# umodular_ctrl16.net
KiCad netlist of a schematic drawn in EAGLE
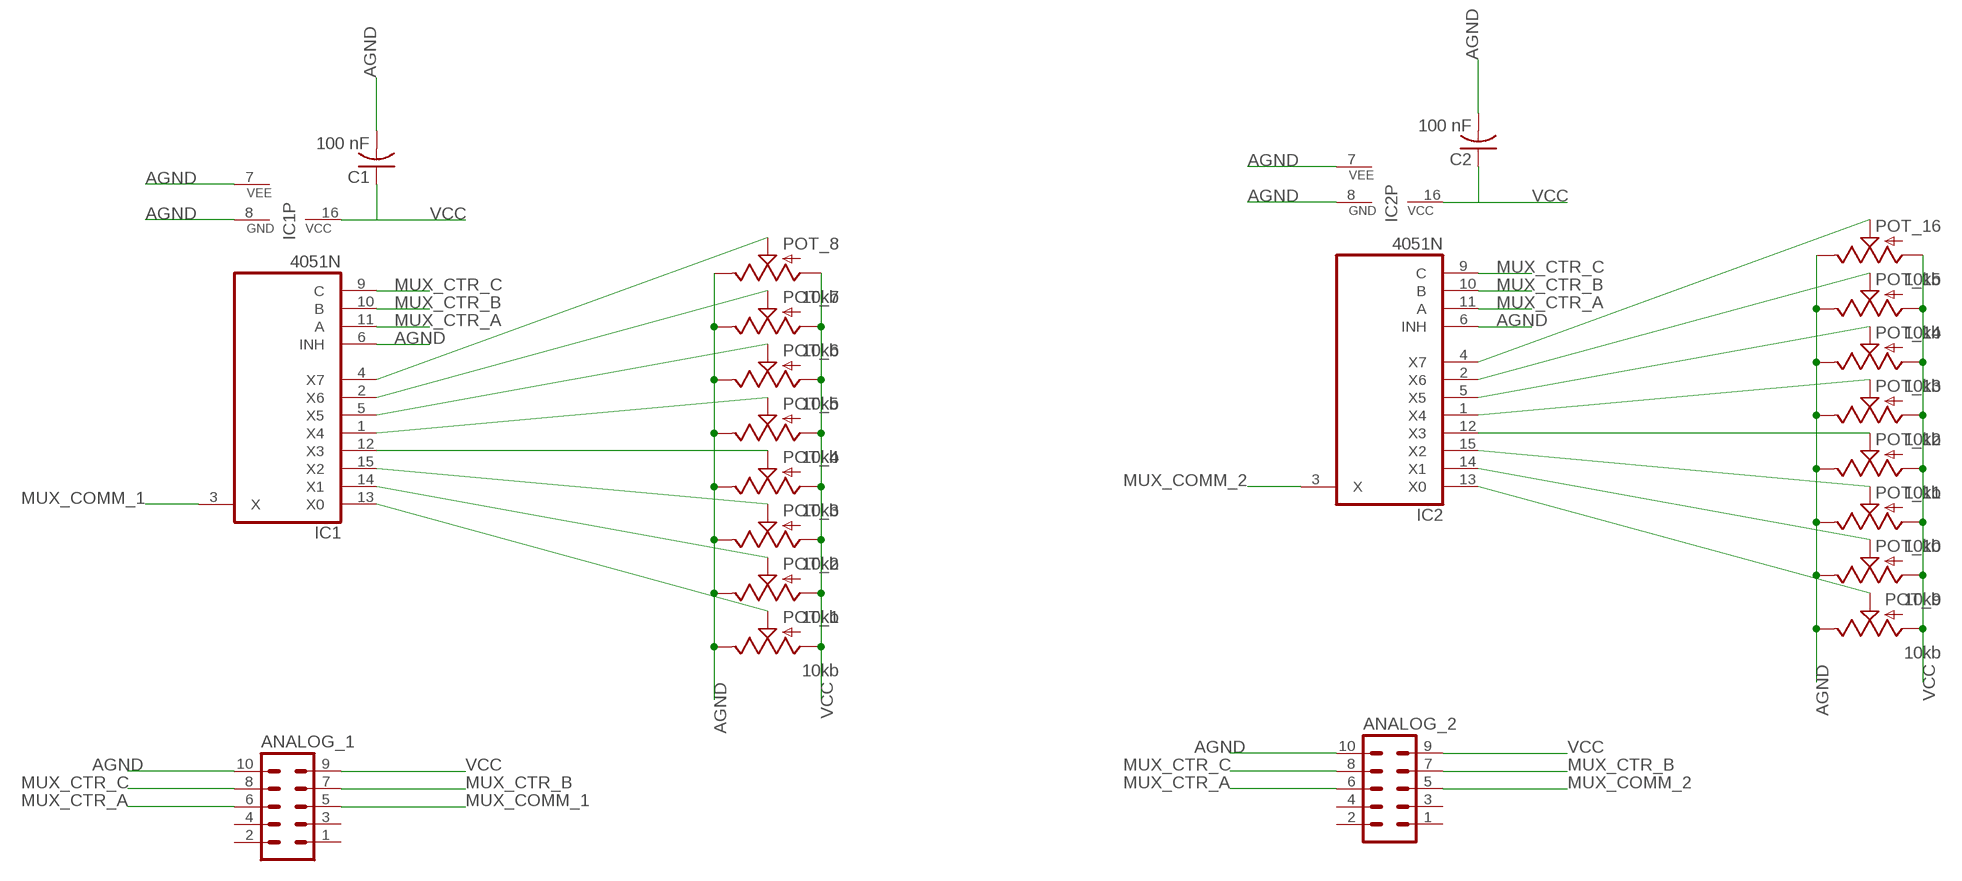
[diagram p0: schematic, sheet 1]
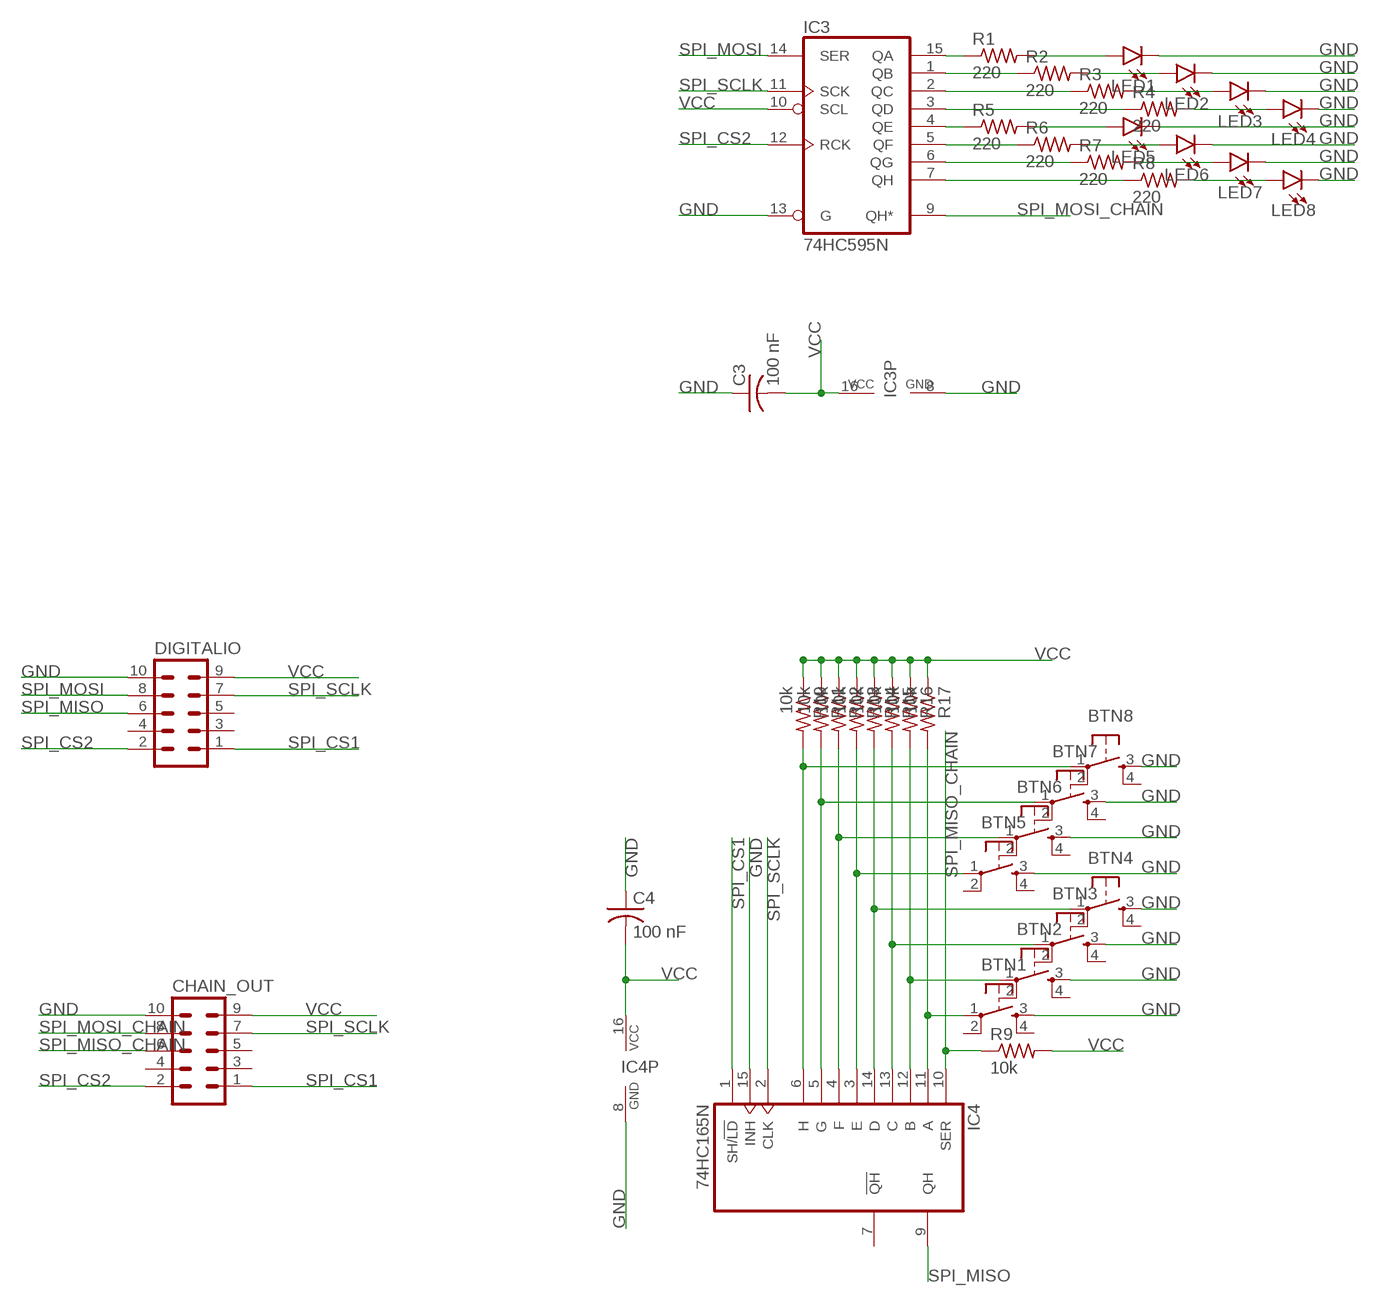
[diagram p1: schematic, sheet 2]

(export (version "E")
  (design (tool "Eeschema 10.0.6"))
  (components
    (comp (ref "ANALOG_1")
      (value "MA05-2")
      (footprint "eagle-import:MA05-2")
      (libsource (lib "eagle-import") (part "MA05-2"))
    )
    (comp (ref "ANALOG_2")
      (value "MA05-2")
      (footprint "eagle-import:MA05-2")
      (libsource (lib "eagle-import") (part "MA05-2"))
    )
    (comp (ref "C1")
      (value "100 nF")
      (footprint "eagle-import:C050-024X044")
      (libsource (lib "eagle-import") (part "C-US050-024X044"))
    )
    (comp (ref "C2")
      (value "100 nF")
      (footprint "eagle-import:C050-024X044")
      (libsource (lib "eagle-import") (part "C-US050-024X044"))
    )
    (comp (ref "IC1")
      (value "4051N")
      (footprint "eagle-import:DIL16")
      (libsource (lib "eagle-import") (part "4051N"))
    )
    (comp (ref "IC2")
      (value "4051N")
      (footprint "eagle-import:DIL16")
      (libsource (lib "eagle-import") (part "4051N"))
    )
    (comp (ref "POT_1")
      (value "10kb")
      (footprint "eagle-import:ALPS_POT")
      (libsource (lib "eagle-import") (part "POT"))
    )
    (comp (ref "POT_2")
      (value "10kb")
      (footprint "eagle-import:ALPS_POT")
      (libsource (lib "eagle-import") (part "POT"))
    )
    (comp (ref "POT_3")
      (value "10kb")
      (footprint "eagle-import:ALPS_POT")
      (libsource (lib "eagle-import") (part "POT"))
    )
    (comp (ref "POT_4")
      (value "10kb")
      (footprint "eagle-import:ALPS_POT")
      (libsource (lib "eagle-import") (part "POT"))
    )
    (comp (ref "POT_5")
      (value "10kb")
      (footprint "eagle-import:ALPS_POT")
      (libsource (lib "eagle-import") (part "POT"))
    )
    (comp (ref "POT_6")
      (value "10kb")
      (footprint "eagle-import:ALPS_POT")
      (libsource (lib "eagle-import") (part "POT"))
    )
    (comp (ref "POT_7")
      (value "10kb")
      (footprint "eagle-import:ALPS_POT")
      (libsource (lib "eagle-import") (part "POT"))
    )
    (comp (ref "POT_8")
      (value "10kb")
      (footprint "eagle-import:ALPS_POT")
      (libsource (lib "eagle-import") (part "POT"))
    )
    (comp (ref "POT_9")
      (value "10kb")
      (footprint "eagle-import:ALPS_POT")
      (libsource (lib "eagle-import") (part "POT"))
    )
    (comp (ref "POT_10")
      (value "10kb")
      (footprint "eagle-import:ALPS_POT")
      (libsource (lib "eagle-import") (part "POT"))
    )
    (comp (ref "POT_11")
      (value "10kb")
      (footprint "eagle-import:ALPS_POT")
      (libsource (lib "eagle-import") (part "POT"))
    )
    (comp (ref "POT_12")
      (value "10kb")
      (footprint "eagle-import:ALPS_POT")
      (libsource (lib "eagle-import") (part "POT"))
    )
    (comp (ref "POT_13")
      (value "10kb")
      (footprint "eagle-import:ALPS_POT")
      (libsource (lib "eagle-import") (part "POT"))
    )
    (comp (ref "POT_14")
      (value "10kb")
      (footprint "eagle-import:ALPS_POT")
      (libsource (lib "eagle-import") (part "POT"))
    )
    (comp (ref "POT_15")
      (value "10kb")
      (footprint "eagle-import:ALPS_POT")
      (libsource (lib "eagle-import") (part "POT"))
    )
    (comp (ref "POT_16")
      (value "10kb")
      (footprint "eagle-import:ALPS_POT")
      (libsource (lib "eagle-import") (part "POT"))
    )
    (comp (ref "BTN1")
      (value "TAC_SWITCHPTH")
      (footprint "eagle-import:TACTILE-PTH")
      (libsource (lib "eagle-import") (part "TAC_SWITCHPTH"))
    )
    (comp (ref "BTN2")
      (value "TAC_SWITCHPTH")
      (footprint "eagle-import:TACTILE-PTH")
      (libsource (lib "eagle-import") (part "TAC_SWITCHPTH"))
    )
    (comp (ref "BTN3")
      (value "TAC_SWITCHPTH")
      (footprint "eagle-import:TACTILE-PTH")
      (libsource (lib "eagle-import") (part "TAC_SWITCHPTH"))
    )
    (comp (ref "BTN4")
      (value "TAC_SWITCHPTH")
      (footprint "eagle-import:TACTILE-PTH")
      (libsource (lib "eagle-import") (part "TAC_SWITCHPTH"))
    )
    (comp (ref "BTN5")
      (value "TAC_SWITCHPTH")
      (footprint "eagle-import:TACTILE-PTH")
      (libsource (lib "eagle-import") (part "TAC_SWITCHPTH"))
    )
    (comp (ref "BTN6")
      (value "TAC_SWITCHPTH")
      (footprint "eagle-import:TACTILE-PTH")
      (libsource (lib "eagle-import") (part "TAC_SWITCHPTH"))
    )
    (comp (ref "BTN7")
      (value "TAC_SWITCHPTH")
      (footprint "eagle-import:TACTILE-PTH")
      (libsource (lib "eagle-import") (part "TAC_SWITCHPTH"))
    )
    (comp (ref "BTN8")
      (value "TAC_SWITCHPTH")
      (footprint "eagle-import:TACTILE-PTH")
      (libsource (lib "eagle-import") (part "TAC_SWITCHPTH"))
    )
    (comp (ref "C3")
      (value "100 nF")
      (footprint "eagle-import:C050-024X044")
      (libsource (lib "eagle-import") (part "C-US050-024X044"))
    )
    (comp (ref "C4")
      (value "100 nF")
      (footprint "eagle-import:C050-024X044")
      (libsource (lib "eagle-import") (part "C-US050-024X044"))
    )
    (comp (ref "CHAIN_OUT")
      (value "MA05-2")
      (footprint "eagle-import:MA05-2")
      (libsource (lib "eagle-import") (part "MA05-2"))
    )
    (comp (ref "DIGITALIO")
      (value "MA05-2")
      (footprint "eagle-import:MA05-2")
      (libsource (lib "eagle-import") (part "MA05-2"))
    )
    (comp (ref "IC3")
      (value "74HC595N")
      (footprint "eagle-import:DIL16")
      (libsource (lib "eagle-import") (part "74595NHC"))
    )
    (comp (ref "IC4")
      (value "74HC165N")
      (footprint "eagle-import:DIL16")
      (libsource (lib "eagle-import") (part "74165NHC"))
    )
    (comp (ref "LED1")
      (value "LED3MM")
      (footprint "eagle-import:LED_3MM")
      (libsource (lib "eagle-import") (part "LED3MM"))
    )
    (comp (ref "LED2")
      (value "LED3MM")
      (footprint "eagle-import:LED_3MM")
      (libsource (lib "eagle-import") (part "LED3MM"))
    )
    (comp (ref "LED3")
      (value "LED3MM")
      (footprint "eagle-import:LED_3MM")
      (libsource (lib "eagle-import") (part "LED3MM"))
    )
    (comp (ref "LED4")
      (value "LED3MM")
      (footprint "eagle-import:LED_3MM")
      (libsource (lib "eagle-import") (part "LED3MM"))
    )
    (comp (ref "LED5")
      (value "LED3MM")
      (footprint "eagle-import:LED_3MM")
      (libsource (lib "eagle-import") (part "LED3MM"))
    )
    (comp (ref "LED6")
      (value "LED3MM")
      (footprint "eagle-import:LED_3MM")
      (libsource (lib "eagle-import") (part "LED3MM"))
    )
    (comp (ref "LED7")
      (value "LED3MM")
      (footprint "eagle-import:LED_3MM")
      (libsource (lib "eagle-import") (part "LED3MM"))
    )
    (comp (ref "LED8")
      (value "LED3MM")
      (footprint "eagle-import:LED_3MM")
      (libsource (lib "eagle-import") (part "LED3MM"))
    )
    (comp (ref "R1")
      (value "220")
      (footprint "eagle-import:0204_7")
      (libsource (lib "eagle-import") (part "R-US_0204/7"))
    )
    (comp (ref "R2")
      (value "220")
      (footprint "eagle-import:0204_7")
      (libsource (lib "eagle-import") (part "R-US_0204/7"))
    )
    (comp (ref "R3")
      (value "220")
      (footprint "eagle-import:0204_7")
      (libsource (lib "eagle-import") (part "R-US_0204/7"))
    )
    (comp (ref "R4")
      (value "220")
      (footprint "eagle-import:0204_7")
      (libsource (lib "eagle-import") (part "R-US_0204/7"))
    )
    (comp (ref "R5")
      (value "220")
      (footprint "eagle-import:0204_7")
      (libsource (lib "eagle-import") (part "R-US_0204/7"))
    )
    (comp (ref "R6")
      (value "220")
      (footprint "eagle-import:0204_7")
      (libsource (lib "eagle-import") (part "R-US_0204/7"))
    )
    (comp (ref "R7")
      (value "220")
      (footprint "eagle-import:0204_7")
      (libsource (lib "eagle-import") (part "R-US_0204/7"))
    )
    (comp (ref "R8")
      (value "220")
      (footprint "eagle-import:0204_7")
      (libsource (lib "eagle-import") (part "R-US_0204/7"))
    )
    (comp (ref "R9")
      (value "10k")
      (footprint "eagle-import:0204_7")
      (libsource (lib "eagle-import") (part "resistor_R-US_0204/7"))
    )
    (comp (ref "R10")
      (value "10k")
      (footprint "eagle-import:0204_7")
      (libsource (lib "eagle-import") (part "resistor_R-US_0204/7"))
    )
    (comp (ref "R11")
      (value "10k")
      (footprint "eagle-import:0204_7")
      (libsource (lib "eagle-import") (part "resistor_R-US_0204/7"))
    )
    (comp (ref "R12")
      (value "10k")
      (footprint "eagle-import:0204_7")
      (libsource (lib "eagle-import") (part "resistor_R-US_0204/7"))
    )
    (comp (ref "R13")
      (value "10k")
      (footprint "eagle-import:0204_7")
      (libsource (lib "eagle-import") (part "resistor_R-US_0204/7"))
    )
    (comp (ref "R14")
      (value "10k")
      (footprint "eagle-import:0204_7")
      (libsource (lib "eagle-import") (part "resistor_R-US_0204/7"))
    )
    (comp (ref "R15")
      (value "10k")
      (footprint "eagle-import:0204_7")
      (libsource (lib "eagle-import") (part "resistor_R-US_0204/7"))
    )
    (comp (ref "R16")
      (value "10k")
      (footprint "eagle-import:0204_7")
      (libsource (lib "eagle-import") (part "resistor_R-US_0204/7"))
    )
    (comp (ref "R17")
      (value "10k")
      (footprint "eagle-import:0204_7")
      (libsource (lib "eagle-import") (part "resistor_R-US_0204/7"))
    )
  )
  (nets
    (net (code "1") (name "AGND") (class "Default")
      (node (ref "ANALOG_1") (pin "10") (pinfunction "10_10") (pintype "passive"))
      (node (ref "ANALOG_2") (pin "10") (pinfunction "10_10") (pintype "passive"))
      (node (ref "C1") (pin "2") (pinfunction "2_2") (pintype "passive"))
      (node (ref "C2") (pin "2") (pinfunction "2_2") (pintype "passive"))
      (node (ref "IC1") (pin "6") (pinfunction "INH_6") (pintype "input"))
      (node (ref "IC1") (pin "7") (pinfunction "VEE_7") (pintype "power_in"))
      (node (ref "IC1") (pin "8") (pinfunction "GND_8") (pintype "power_in"))
      (node (ref "IC2") (pin "6") (pinfunction "INH_6") (pintype "input"))
      (node (ref "IC2") (pin "7") (pinfunction "VEE_7") (pintype "power_in"))
      (node (ref "IC2") (pin "8") (pinfunction "GND_8") (pintype "power_in"))
      (node (ref "POT_1") (pin "P$1") (pinfunction "E_P$1") (pintype "passive"))
      (node (ref "POT_10") (pin "P$1") (pinfunction "E_P$1") (pintype "passive"))
      (node (ref "POT_11") (pin "P$1") (pinfunction "E_P$1") (pintype "passive"))
      (node (ref "POT_12") (pin "P$1") (pinfunction "E_P$1") (pintype "passive"))
      (node (ref "POT_13") (pin "P$1") (pinfunction "E_P$1") (pintype "passive"))
      (node (ref "POT_14") (pin "P$1") (pinfunction "E_P$1") (pintype "passive"))
      (node (ref "POT_15") (pin "P$1") (pinfunction "E_P$1") (pintype "passive"))
      (node (ref "POT_16") (pin "P$1") (pinfunction "E_P$1") (pintype "passive"))
      (node (ref "POT_2") (pin "P$1") (pinfunction "E_P$1") (pintype "passive"))
      (node (ref "POT_3") (pin "P$1") (pinfunction "E_P$1") (pintype "passive"))
      (node (ref "POT_4") (pin "P$1") (pinfunction "E_P$1") (pintype "passive"))
      (node (ref "POT_5") (pin "P$1") (pinfunction "E_P$1") (pintype "passive"))
      (node (ref "POT_6") (pin "P$1") (pinfunction "E_P$1") (pintype "passive"))
      (node (ref "POT_7") (pin "P$1") (pinfunction "E_P$1") (pintype "passive"))
      (node (ref "POT_8") (pin "P$1") (pinfunction "E_P$1") (pintype "passive"))
      (node (ref "POT_9") (pin "P$1") (pinfunction "E_P$1") (pintype "passive"))
    )
    (net (code "2") (name "GND") (class "Default")
      (node (ref "BTN1") (pin "3") (pinfunction "3_3") (pintype "passive"))
      (node (ref "BTN2") (pin "3") (pinfunction "3_3") (pintype "passive"))
      (node (ref "BTN3") (pin "3") (pinfunction "3_3") (pintype "passive"))
      (node (ref "BTN4") (pin "3") (pinfunction "3_3") (pintype "passive"))
      (node (ref "BTN5") (pin "3") (pinfunction "3_3") (pintype "passive"))
      (node (ref "BTN6") (pin "3") (pinfunction "3_3") (pintype "passive"))
      (node (ref "BTN7") (pin "3") (pinfunction "3_3") (pintype "passive"))
      (node (ref "BTN8") (pin "3") (pinfunction "3_3") (pintype "passive"))
      (node (ref "C3") (pin "1") (pinfunction "1_1") (pintype "passive"))
      (node (ref "C4") (pin "1") (pinfunction "1_1") (pintype "passive"))
      (node (ref "CHAIN_OUT") (pin "10") (pinfunction "10_10") (pintype "passive"))
      (node (ref "DIGITALIO") (pin "10") (pinfunction "10_10") (pintype "passive"))
      (node (ref "IC3") (pin "13") (pinfunction "G_13") (pintype "input"))
      (node (ref "IC3") (pin "8") (pinfunction "GND_8") (pintype "power_in"))
      (node (ref "IC4") (pin "15") (pinfunction "INH_15") (pintype "input"))
      (node (ref "IC4") (pin "8") (pinfunction "GND_8") (pintype "power_in"))
      (node (ref "LED1") (pin "K") (pinfunction "C_K") (pintype "passive"))
      (node (ref "LED2") (pin "K") (pinfunction "C_K") (pintype "passive"))
      (node (ref "LED3") (pin "K") (pinfunction "C_K") (pintype "passive"))
      (node (ref "LED4") (pin "K") (pinfunction "C_K") (pintype "passive"))
      (node (ref "LED5") (pin "K") (pinfunction "C_K") (pintype "passive"))
      (node (ref "LED6") (pin "K") (pinfunction "C_K") (pintype "passive"))
      (node (ref "LED7") (pin "K") (pinfunction "C_K") (pintype "passive"))
      (node (ref "LED8") (pin "K") (pinfunction "C_K") (pintype "passive"))
    )
    (net (code "3") (name "MUX_COMM_1") (class "Default")
      (node (ref "ANALOG_1") (pin "5") (pinfunction "5_5") (pintype "passive"))
      (node (ref "IC1") (pin "3") (pinfunction "X_3") (pintype "bidirectional"))
    )
    (net (code "4") (name "MUX_COMM_2") (class "Default")
      (node (ref "ANALOG_2") (pin "5") (pinfunction "5_5") (pintype "passive"))
      (node (ref "IC2") (pin "3") (pinfunction "X_3") (pintype "bidirectional"))
    )
    (net (code "5") (name "MUX_CTR_A") (class "Default")
      (node (ref "ANALOG_1") (pin "6") (pinfunction "6_6") (pintype "passive"))
      (node (ref "ANALOG_2") (pin "6") (pinfunction "6_6") (pintype "passive"))
      (node (ref "IC1") (pin "11") (pinfunction "A_11") (pintype "input"))
      (node (ref "IC2") (pin "11") (pinfunction "A_11") (pintype "input"))
    )
    (net (code "6") (name "MUX_CTR_B") (class "Default")
      (node (ref "ANALOG_1") (pin "7") (pinfunction "7_7") (pintype "passive"))
      (node (ref "ANALOG_2") (pin "7") (pinfunction "7_7") (pintype "passive"))
      (node (ref "IC1") (pin "10") (pinfunction "B_10") (pintype "input"))
      (node (ref "IC2") (pin "10") (pinfunction "B_10") (pintype "input"))
    )
    (net (code "7") (name "MUX_CTR_C") (class "Default")
      (node (ref "ANALOG_1") (pin "8") (pinfunction "8_8") (pintype "passive"))
      (node (ref "ANALOG_2") (pin "8") (pinfunction "8_8") (pintype "passive"))
      (node (ref "IC1") (pin "9") (pinfunction "C_9") (pintype "input"))
      (node (ref "IC2") (pin "9") (pinfunction "C_9") (pintype "input"))
    )
    (net (code "8") (name "Net-(IC1A-X0)") (class "Default")
      (node (ref "IC1") (pin "13") (pinfunction "X0_13") (pintype "bidirectional"))
      (node (ref "POT_1") (pin "P$2") (pinfunction "S_P$2") (pintype "passive"))
    )
    (net (code "9") (name "Net-(IC1A-X1)") (class "Default")
      (node (ref "IC1") (pin "14") (pinfunction "X1_14") (pintype "bidirectional"))
      (node (ref "POT_2") (pin "P$2") (pinfunction "S_P$2") (pintype "passive"))
    )
    (net (code "10") (name "Net-(IC1A-X2)") (class "Default")
      (node (ref "IC1") (pin "15") (pinfunction "X2_15") (pintype "bidirectional"))
      (node (ref "POT_3") (pin "P$2") (pinfunction "S_P$2") (pintype "passive"))
    )
    (net (code "11") (name "Net-(IC1A-X3)") (class "Default")
      (node (ref "IC1") (pin "12") (pinfunction "X3_12") (pintype "bidirectional"))
      (node (ref "POT_4") (pin "P$2") (pinfunction "S_P$2") (pintype "passive"))
    )
    (net (code "12") (name "Net-(IC1A-X4)") (class "Default")
      (node (ref "IC1") (pin "1") (pinfunction "X4_1") (pintype "bidirectional"))
      (node (ref "POT_5") (pin "P$2") (pinfunction "S_P$2") (pintype "passive"))
    )
    (net (code "13") (name "Net-(IC1A-X5)") (class "Default")
      (node (ref "IC1") (pin "5") (pinfunction "X5_5") (pintype "bidirectional"))
      (node (ref "POT_6") (pin "P$2") (pinfunction "S_P$2") (pintype "passive"))
    )
    (net (code "14") (name "Net-(IC1A-X6)") (class "Default")
      (node (ref "IC1") (pin "2") (pinfunction "X6_2") (pintype "bidirectional"))
      (node (ref "POT_7") (pin "P$2") (pinfunction "S_P$2") (pintype "passive"))
    )
    (net (code "15") (name "Net-(IC1A-X7)") (class "Default")
      (node (ref "IC1") (pin "4") (pinfunction "X7_4") (pintype "bidirectional"))
      (node (ref "POT_8") (pin "P$2") (pinfunction "S_P$2") (pintype "passive"))
    )
    (net (code "16") (name "Net-(IC2A-X0)") (class "Default")
      (node (ref "IC2") (pin "13") (pinfunction "X0_13") (pintype "bidirectional"))
      (node (ref "POT_9") (pin "P$2") (pinfunction "S_P$2") (pintype "passive"))
    )
    (net (code "17") (name "Net-(IC2A-X1)") (class "Default")
      (node (ref "IC2") (pin "14") (pinfunction "X1_14") (pintype "bidirectional"))
      (node (ref "POT_10") (pin "P$2") (pinfunction "S_P$2") (pintype "passive"))
    )
    (net (code "18") (name "Net-(IC2A-X2)") (class "Default")
      (node (ref "IC2") (pin "15") (pinfunction "X2_15") (pintype "bidirectional"))
      (node (ref "POT_11") (pin "P$2") (pinfunction "S_P$2") (pintype "passive"))
    )
    (net (code "19") (name "Net-(IC2A-X3)") (class "Default")
      (node (ref "IC2") (pin "12") (pinfunction "X3_12") (pintype "bidirectional"))
      (node (ref "POT_12") (pin "P$2") (pinfunction "S_P$2") (pintype "passive"))
    )
    (net (code "20") (name "Net-(IC2A-X4)") (class "Default")
      (node (ref "IC2") (pin "1") (pinfunction "X4_1") (pintype "bidirectional"))
      (node (ref "POT_13") (pin "P$2") (pinfunction "S_P$2") (pintype "passive"))
    )
    (net (code "21") (name "Net-(IC2A-X5)") (class "Default")
      (node (ref "IC2") (pin "5") (pinfunction "X5_5") (pintype "bidirectional"))
      (node (ref "POT_14") (pin "P$2") (pinfunction "S_P$2") (pintype "passive"))
    )
    (net (code "22") (name "Net-(IC2A-X6)") (class "Default")
      (node (ref "IC2") (pin "2") (pinfunction "X6_2") (pintype "bidirectional"))
      (node (ref "POT_15") (pin "P$2") (pinfunction "S_P$2") (pintype "passive"))
    )
    (net (code "23") (name "Net-(IC2A-X7)") (class "Default")
      (node (ref "IC2") (pin "4") (pinfunction "X7_4") (pintype "bidirectional"))
      (node (ref "POT_16") (pin "P$2") (pinfunction "S_P$2") (pintype "passive"))
    )
    (net (code "24") (name "Net-(IC3A-QA)") (class "Default")
      (node (ref "IC3") (pin "15") (pinfunction "QA_15") (pintype "tri_state"))
      (node (ref "R1") (pin "1") (pinfunction "1_1") (pintype "passive"))
    )
    (net (code "25") (name "Net-(IC3A-QB)") (class "Default")
      (node (ref "IC3") (pin "1") (pinfunction "QB_1") (pintype "tri_state"))
      (node (ref "R2") (pin "1") (pinfunction "1_1") (pintype "passive"))
    )
    (net (code "26") (name "Net-(IC3A-QC)") (class "Default")
      (node (ref "IC3") (pin "2") (pinfunction "QC_2") (pintype "tri_state"))
      (node (ref "R3") (pin "1") (pinfunction "1_1") (pintype "passive"))
    )
    (net (code "27") (name "Net-(IC3A-QD)") (class "Default")
      (node (ref "IC3") (pin "3") (pinfunction "QD_3") (pintype "tri_state"))
      (node (ref "R4") (pin "1") (pinfunction "1_1") (pintype "passive"))
    )
    (net (code "28") (name "Net-(IC3A-QE)") (class "Default")
      (node (ref "IC3") (pin "4") (pinfunction "QE_4") (pintype "tri_state"))
      (node (ref "R5") (pin "1") (pinfunction "1_1") (pintype "passive"))
    )
    (net (code "29") (name "Net-(IC3A-QF)") (class "Default")
      (node (ref "IC3") (pin "5") (pinfunction "QF_5") (pintype "tri_state"))
      (node (ref "R6") (pin "1") (pinfunction "1_1") (pintype "passive"))
    )
    (net (code "30") (name "Net-(IC3A-QG)") (class "Default")
      (node (ref "IC3") (pin "6") (pinfunction "QG_6") (pintype "tri_state"))
      (node (ref "R7") (pin "1") (pinfunction "1_1") (pintype "passive"))
    )
    (net (code "31") (name "Net-(IC3A-QH)") (class "Default")
      (node (ref "IC3") (pin "7") (pinfunction "QH_7") (pintype "tri_state"))
      (node (ref "R8") (pin "1") (pinfunction "1_1") (pintype "passive"))
    )
    (net (code "32") (name "Net-(IC4A-A)") (class "Default")
      (node (ref "BTN1") (pin "1") (pinfunction "1_1") (pintype "passive"))
      (node (ref "IC4") (pin "11") (pinfunction "A_11") (pintype "input"))
      (node (ref "R17") (pin "2") (pinfunction "2_2") (pintype "passive"))
    )
    (net (code "33") (name "Net-(IC4A-B)") (class "Default")
      (node (ref "BTN2") (pin "1") (pinfunction "1_1") (pintype "passive"))
      (node (ref "IC4") (pin "12") (pinfunction "B_12") (pintype "input"))
      (node (ref "R16") (pin "2") (pinfunction "2_2") (pintype "passive"))
    )
    (net (code "34") (name "Net-(IC4A-C)") (class "Default")
      (node (ref "BTN3") (pin "1") (pinfunction "1_1") (pintype "passive"))
      (node (ref "IC4") (pin "13") (pinfunction "C_13") (pintype "input"))
      (node (ref "R15") (pin "2") (pinfunction "2_2") (pintype "passive"))
    )
    (net (code "35") (name "Net-(IC4A-D)") (class "Default")
      (node (ref "BTN4") (pin "1") (pinfunction "1_1") (pintype "passive"))
      (node (ref "IC4") (pin "14") (pinfunction "D_14") (pintype "input"))
      (node (ref "R14") (pin "2") (pinfunction "2_2") (pintype "passive"))
    )
    (net (code "36") (name "Net-(IC4A-E)") (class "Default")
      (node (ref "BTN5") (pin "1") (pinfunction "1_1") (pintype "passive"))
      (node (ref "IC4") (pin "3") (pinfunction "E_3") (pintype "input"))
      (node (ref "R13") (pin "2") (pinfunction "2_2") (pintype "passive"))
    )
    (net (code "37") (name "Net-(IC4A-F)") (class "Default")
      (node (ref "BTN6") (pin "1") (pinfunction "1_1") (pintype "passive"))
      (node (ref "IC4") (pin "4") (pinfunction "F_4") (pintype "input"))
      (node (ref "R12") (pin "2") (pinfunction "2_2") (pintype "passive"))
    )
    (net (code "38") (name "Net-(IC4A-G)") (class "Default")
      (node (ref "BTN7") (pin "1") (pinfunction "1_1") (pintype "passive"))
      (node (ref "IC4") (pin "5") (pinfunction "G_5") (pintype "input"))
      (node (ref "R11") (pin "2") (pinfunction "2_2") (pintype "passive"))
    )
    (net (code "39") (name "Net-(IC4A-H)") (class "Default")
      (node (ref "BTN8") (pin "1") (pinfunction "1_1") (pintype "passive"))
      (node (ref "IC4") (pin "6") (pinfunction "H_6") (pintype "input"))
      (node (ref "R10") (pin "2") (pinfunction "2_2") (pintype "passive"))
    )
    (net (code "40") (name "Net-(LED1-PadA)") (class "Default")
      (node (ref "LED1") (pin "A") (pinfunction "A_A") (pintype "passive"))
      (node (ref "R1") (pin "2") (pinfunction "2_2") (pintype "passive"))
    )
    (net (code "41") (name "Net-(LED2-PadA)") (class "Default")
      (node (ref "LED2") (pin "A") (pinfunction "A_A") (pintype "passive"))
      (node (ref "R2") (pin "2") (pinfunction "2_2") (pintype "passive"))
    )
    (net (code "42") (name "Net-(LED3-PadA)") (class "Default")
      (node (ref "LED3") (pin "A") (pinfunction "A_A") (pintype "passive"))
      (node (ref "R3") (pin "2") (pinfunction "2_2") (pintype "passive"))
    )
    (net (code "43") (name "Net-(LED4-PadA)") (class "Default")
      (node (ref "LED4") (pin "A") (pinfunction "A_A") (pintype "passive"))
      (node (ref "R4") (pin "2") (pinfunction "2_2") (pintype "passive"))
    )
    (net (code "44") (name "Net-(LED5-PadA)") (class "Default")
      (node (ref "LED5") (pin "A") (pinfunction "A_A") (pintype "passive"))
      (node (ref "R5") (pin "2") (pinfunction "2_2") (pintype "passive"))
    )
    (net (code "45") (name "Net-(LED6-PadA)") (class "Default")
      (node (ref "LED6") (pin "A") (pinfunction "A_A") (pintype "passive"))
      (node (ref "R6") (pin "2") (pinfunction "2_2") (pintype "passive"))
    )
    (net (code "46") (name "Net-(LED7-PadA)") (class "Default")
      (node (ref "LED7") (pin "A") (pinfunction "A_A") (pintype "passive"))
      (node (ref "R7") (pin "2") (pinfunction "2_2") (pintype "passive"))
    )
    (net (code "47") (name "Net-(LED8-PadA)") (class "Default")
      (node (ref "LED8") (pin "A") (pinfunction "A_A") (pintype "passive"))
      (node (ref "R8") (pin "2") (pinfunction "2_2") (pintype "passive"))
    )
    (net (code "48") (name "SPI_CS1") (class "Default")
      (node (ref "CHAIN_OUT") (pin "1") (pinfunction "1_1") (pintype "passive"))
      (node (ref "DIGITALIO") (pin "1") (pinfunction "1_1") (pintype "passive"))
      (node (ref "IC4") (pin "1") (pinfunction "SH/~{LD}_1") (pintype "input"))
    )
    (net (code "49") (name "SPI_CS2") (class "Default")
      (node (ref "CHAIN_OUT") (pin "2") (pinfunction "2_2") (pintype "passive"))
      (node (ref "DIGITALIO") (pin "2") (pinfunction "2_2") (pintype "passive"))
      (node (ref "IC3") (pin "12") (pinfunction "RCK_12") (pintype "input"))
    )
    (net (code "50") (name "SPI_MISO") (class "Default")
      (node (ref "DIGITALIO") (pin "6") (pinfunction "6_6") (pintype "passive"))
      (node (ref "IC4") (pin "9") (pinfunction "QH_9") (pintype "output"))
    )
    (net (code "51") (name "SPI_MISO_CHAIN") (class "Default")
      (node (ref "CHAIN_OUT") (pin "6") (pinfunction "6_6") (pintype "passive"))
      (node (ref "IC4") (pin "10") (pinfunction "SER_10") (pintype "input"))
      (node (ref "R9") (pin "1") (pinfunction "1_1") (pintype "passive"))
    )
    (net (code "52") (name "SPI_MOSI") (class "Default")
      (node (ref "DIGITALIO") (pin "8") (pinfunction "8_8") (pintype "passive"))
      (node (ref "IC3") (pin "14") (pinfunction "SER_14") (pintype "input"))
    )
    (net (code "53") (name "SPI_MOSI_CHAIN") (class "Default")
      (node (ref "CHAIN_OUT") (pin "8") (pinfunction "8_8") (pintype "passive"))
      (node (ref "IC3") (pin "9") (pinfunction "QH*_9") (pintype "tri_state"))
    )
    (net (code "54") (name "SPI_SCLK") (class "Default")
      (node (ref "CHAIN_OUT") (pin "7") (pinfunction "7_7") (pintype "passive"))
      (node (ref "DIGITALIO") (pin "7") (pinfunction "7_7") (pintype "passive"))
      (node (ref "IC3") (pin "11") (pinfunction "SCK_11") (pintype "input"))
      (node (ref "IC4") (pin "2") (pinfunction "CLK_2") (pintype "input"))
    )
    (net (code "55") (name "VCC") (class "Default")
      (node (ref "ANALOG_1") (pin "9") (pinfunction "9_9") (pintype "passive"))
      (node (ref "ANALOG_2") (pin "9") (pinfunction "9_9") (pintype "passive"))
      (node (ref "C1") (pin "1") (pinfunction "1_1") (pintype "passive"))
      (node (ref "C2") (pin "1") (pinfunction "1_1") (pintype "passive"))
      (node (ref "C3") (pin "2") (pinfunction "2_2") (pintype "passive"))
      (node (ref "C4") (pin "2") (pinfunction "2_2") (pintype "passive"))
      (node (ref "CHAIN_OUT") (pin "9") (pinfunction "9_9") (pintype "passive"))
      (node (ref "DIGITALIO") (pin "9") (pinfunction "9_9") (pintype "passive"))
      (node (ref "IC1") (pin "16") (pinfunction "VCC_16") (pintype "power_in"))
      (node (ref "IC2") (pin "16") (pinfunction "VCC_16") (pintype "power_in"))
      (node (ref "IC3") (pin "10") (pinfunction "SCL_10") (pintype "input"))
      (node (ref "IC3") (pin "16") (pinfunction "VCC_16") (pintype "power_in"))
      (node (ref "IC4") (pin "16") (pinfunction "VCC_16") (pintype "power_in"))
      (node (ref "POT_1") (pin "P$3") (pinfunction "A_P$3") (pintype "passive"))
      (node (ref "POT_10") (pin "P$3") (pinfunction "A_P$3") (pintype "passive"))
      (node (ref "POT_11") (pin "P$3") (pinfunction "A_P$3") (pintype "passive"))
      (node (ref "POT_12") (pin "P$3") (pinfunction "A_P$3") (pintype "passive"))
      (node (ref "POT_13") (pin "P$3") (pinfunction "A_P$3") (pintype "passive"))
      (node (ref "POT_14") (pin "P$3") (pinfunction "A_P$3") (pintype "passive"))
      (node (ref "POT_15") (pin "P$3") (pinfunction "A_P$3") (pintype "passive"))
      (node (ref "POT_16") (pin "P$3") (pinfunction "A_P$3") (pintype "passive"))
      (node (ref "POT_2") (pin "P$3") (pinfunction "A_P$3") (pintype "passive"))
      (node (ref "POT_3") (pin "P$3") (pinfunction "A_P$3") (pintype "passive"))
      (node (ref "POT_4") (pin "P$3") (pinfunction "A_P$3") (pintype "passive"))
      (node (ref "POT_5") (pin "P$3") (pinfunction "A_P$3") (pintype "passive"))
      (node (ref "POT_6") (pin "P$3") (pinfunction "A_P$3") (pintype "passive"))
      (node (ref "POT_7") (pin "P$3") (pinfunction "A_P$3") (pintype "passive"))
      (node (ref "POT_8") (pin "P$3") (pinfunction "A_P$3") (pintype "passive"))
      (node (ref "POT_9") (pin "P$3") (pinfunction "A_P$3") (pintype "passive"))
      (node (ref "R10") (pin "1") (pinfunction "1_1") (pintype "passive"))
      (node (ref "R11") (pin "1") (pinfunction "1_1") (pintype "passive"))
      (node (ref "R12") (pin "1") (pinfunction "1_1") (pintype "passive"))
      (node (ref "R13") (pin "1") (pinfunction "1_1") (pintype "passive"))
      (node (ref "R14") (pin "1") (pinfunction "1_1") (pintype "passive"))
      (node (ref "R15") (pin "1") (pinfunction "1_1") (pintype "passive"))
      (node (ref "R16") (pin "1") (pinfunction "1_1") (pintype "passive"))
      (node (ref "R17") (pin "1") (pinfunction "1_1") (pintype "passive"))
      (node (ref "R9") (pin "2") (pinfunction "2_2") (pintype "passive"))
    )
    (net (code "56") (name "unconnected-(ANALOG_1-Pad1)") (class "Default")
      (node (ref "ANALOG_1") (pin "1") (pinfunction "1_1") (pintype "passive"))
    )
    (net (code "57") (name "unconnected-(ANALOG_1-Pad2)") (class "Default")
      (node (ref "ANALOG_1") (pin "2") (pinfunction "2_2") (pintype "passive"))
    )
    (net (code "58") (name "unconnected-(ANALOG_1-Pad3)") (class "Default")
      (node (ref "ANALOG_1") (pin "3") (pinfunction "3_3") (pintype "passive"))
    )
    (net (code "59") (name "unconnected-(ANALOG_1-Pad4)") (class "Default")
      (node (ref "ANALOG_1") (pin "4") (pinfunction "4_4") (pintype "passive"))
    )
    (net (code "60") (name "unconnected-(ANALOG_2-Pad1)") (class "Default")
      (node (ref "ANALOG_2") (pin "1") (pinfunction "1_1") (pintype "passive"))
    )
    (net (code "61") (name "unconnected-(ANALOG_2-Pad2)") (class "Default")
      (node (ref "ANALOG_2") (pin "2") (pinfunction "2_2") (pintype "passive"))
    )
    (net (code "62") (name "unconnected-(ANALOG_2-Pad3)") (class "Default")
      (node (ref "ANALOG_2") (pin "3") (pinfunction "3_3") (pintype "passive"))
    )
    (net (code "63") (name "unconnected-(ANALOG_2-Pad4)") (class "Default")
      (node (ref "ANALOG_2") (pin "4") (pinfunction "4_4") (pintype "passive"))
    )
    (net (code "64") (name "unconnected-(BTN1-Pad2)") (class "Default")
      (node (ref "BTN1") (pin "2") (pinfunction "2_2") (pintype "passive"))
    )
    (net (code "65") (name "unconnected-(BTN1-Pad4)") (class "Default")
      (node (ref "BTN1") (pin "4") (pinfunction "4_4") (pintype "passive"))
    )
    (net (code "66") (name "unconnected-(BTN2-Pad2)") (class "Default")
      (node (ref "BTN2") (pin "2") (pinfunction "2_2") (pintype "passive"))
    )
    (net (code "67") (name "unconnected-(BTN2-Pad4)") (class "Default")
      (node (ref "BTN2") (pin "4") (pinfunction "4_4") (pintype "passive"))
    )
    (net (code "68") (name "unconnected-(BTN3-Pad2)") (class "Default")
      (node (ref "BTN3") (pin "2") (pinfunction "2_2") (pintype "passive"))
    )
    (net (code "69") (name "unconnected-(BTN3-Pad4)") (class "Default")
      (node (ref "BTN3") (pin "4") (pinfunction "4_4") (pintype "passive"))
    )
    (net (code "70") (name "unconnected-(BTN4-Pad2)") (class "Default")
      (node (ref "BTN4") (pin "2") (pinfunction "2_2") (pintype "passive"))
    )
    (net (code "71") (name "unconnected-(BTN4-Pad4)") (class "Default")
      (node (ref "BTN4") (pin "4") (pinfunction "4_4") (pintype "passive"))
    )
    (net (code "72") (name "unconnected-(BTN5-Pad2)") (class "Default")
      (node (ref "BTN5") (pin "2") (pinfunction "2_2") (pintype "passive"))
    )
    (net (code "73") (name "unconnected-(BTN5-Pad4)") (class "Default")
      (node (ref "BTN5") (pin "4") (pinfunction "4_4") (pintype "passive"))
    )
    (net (code "74") (name "unconnected-(BTN6-Pad2)") (class "Default")
      (node (ref "BTN6") (pin "2") (pinfunction "2_2") (pintype "passive"))
    )
    (net (code "75") (name "unconnected-(BTN6-Pad4)") (class "Default")
      (node (ref "BTN6") (pin "4") (pinfunction "4_4") (pintype "passive"))
    )
    (net (code "76") (name "unconnected-(BTN7-Pad2)") (class "Default")
      (node (ref "BTN7") (pin "2") (pinfunction "2_2") (pintype "passive"))
    )
    (net (code "77") (name "unconnected-(BTN7-Pad4)") (class "Default")
      (node (ref "BTN7") (pin "4") (pinfunction "4_4") (pintype "passive"))
    )
    (net (code "78") (name "unconnected-(BTN8-Pad2)") (class "Default")
      (node (ref "BTN8") (pin "2") (pinfunction "2_2") (pintype "passive"))
    )
    (net (code "79") (name "unconnected-(BTN8-Pad4)") (class "Default")
      (node (ref "BTN8") (pin "4") (pinfunction "4_4") (pintype "passive"))
    )
    (net (code "80") (name "unconnected-(CHAIN_OUT-Pad3)") (class "Default")
      (node (ref "CHAIN_OUT") (pin "3") (pinfunction "3_3") (pintype "passive"))
    )
    (net (code "81") (name "unconnected-(CHAIN_OUT-Pad4)") (class "Default")
      (node (ref "CHAIN_OUT") (pin "4") (pinfunction "4_4") (pintype "passive"))
    )
    (net (code "82") (name "unconnected-(CHAIN_OUT-Pad5)") (class "Default")
      (node (ref "CHAIN_OUT") (pin "5") (pinfunction "5_5") (pintype "passive"))
    )
    (net (code "83") (name "unconnected-(DIGITALIO-Pad3)") (class "Default")
      (node (ref "DIGITALIO") (pin "3") (pinfunction "3_3") (pintype "passive"))
    )
    (net (code "84") (name "unconnected-(DIGITALIO-Pad4)") (class "Default")
      (node (ref "DIGITALIO") (pin "4") (pinfunction "4_4") (pintype "passive"))
    )
    (net (code "85") (name "unconnected-(DIGITALIO-Pad5)") (class "Default")
      (node (ref "DIGITALIO") (pin "5") (pinfunction "5_5") (pintype "passive"))
    )
    (net (code "86") (name "unconnected-(IC4A-~{QH}-Pad7)") (class "Default")
      (node (ref "IC4") (pin "7") (pinfunction "~{QH}_7") (pintype "output"))
    )
  )
)
